# 2020_Main_Board_-_Schematic.net
KiCad netlist of a schematic drawn in EasyEDA
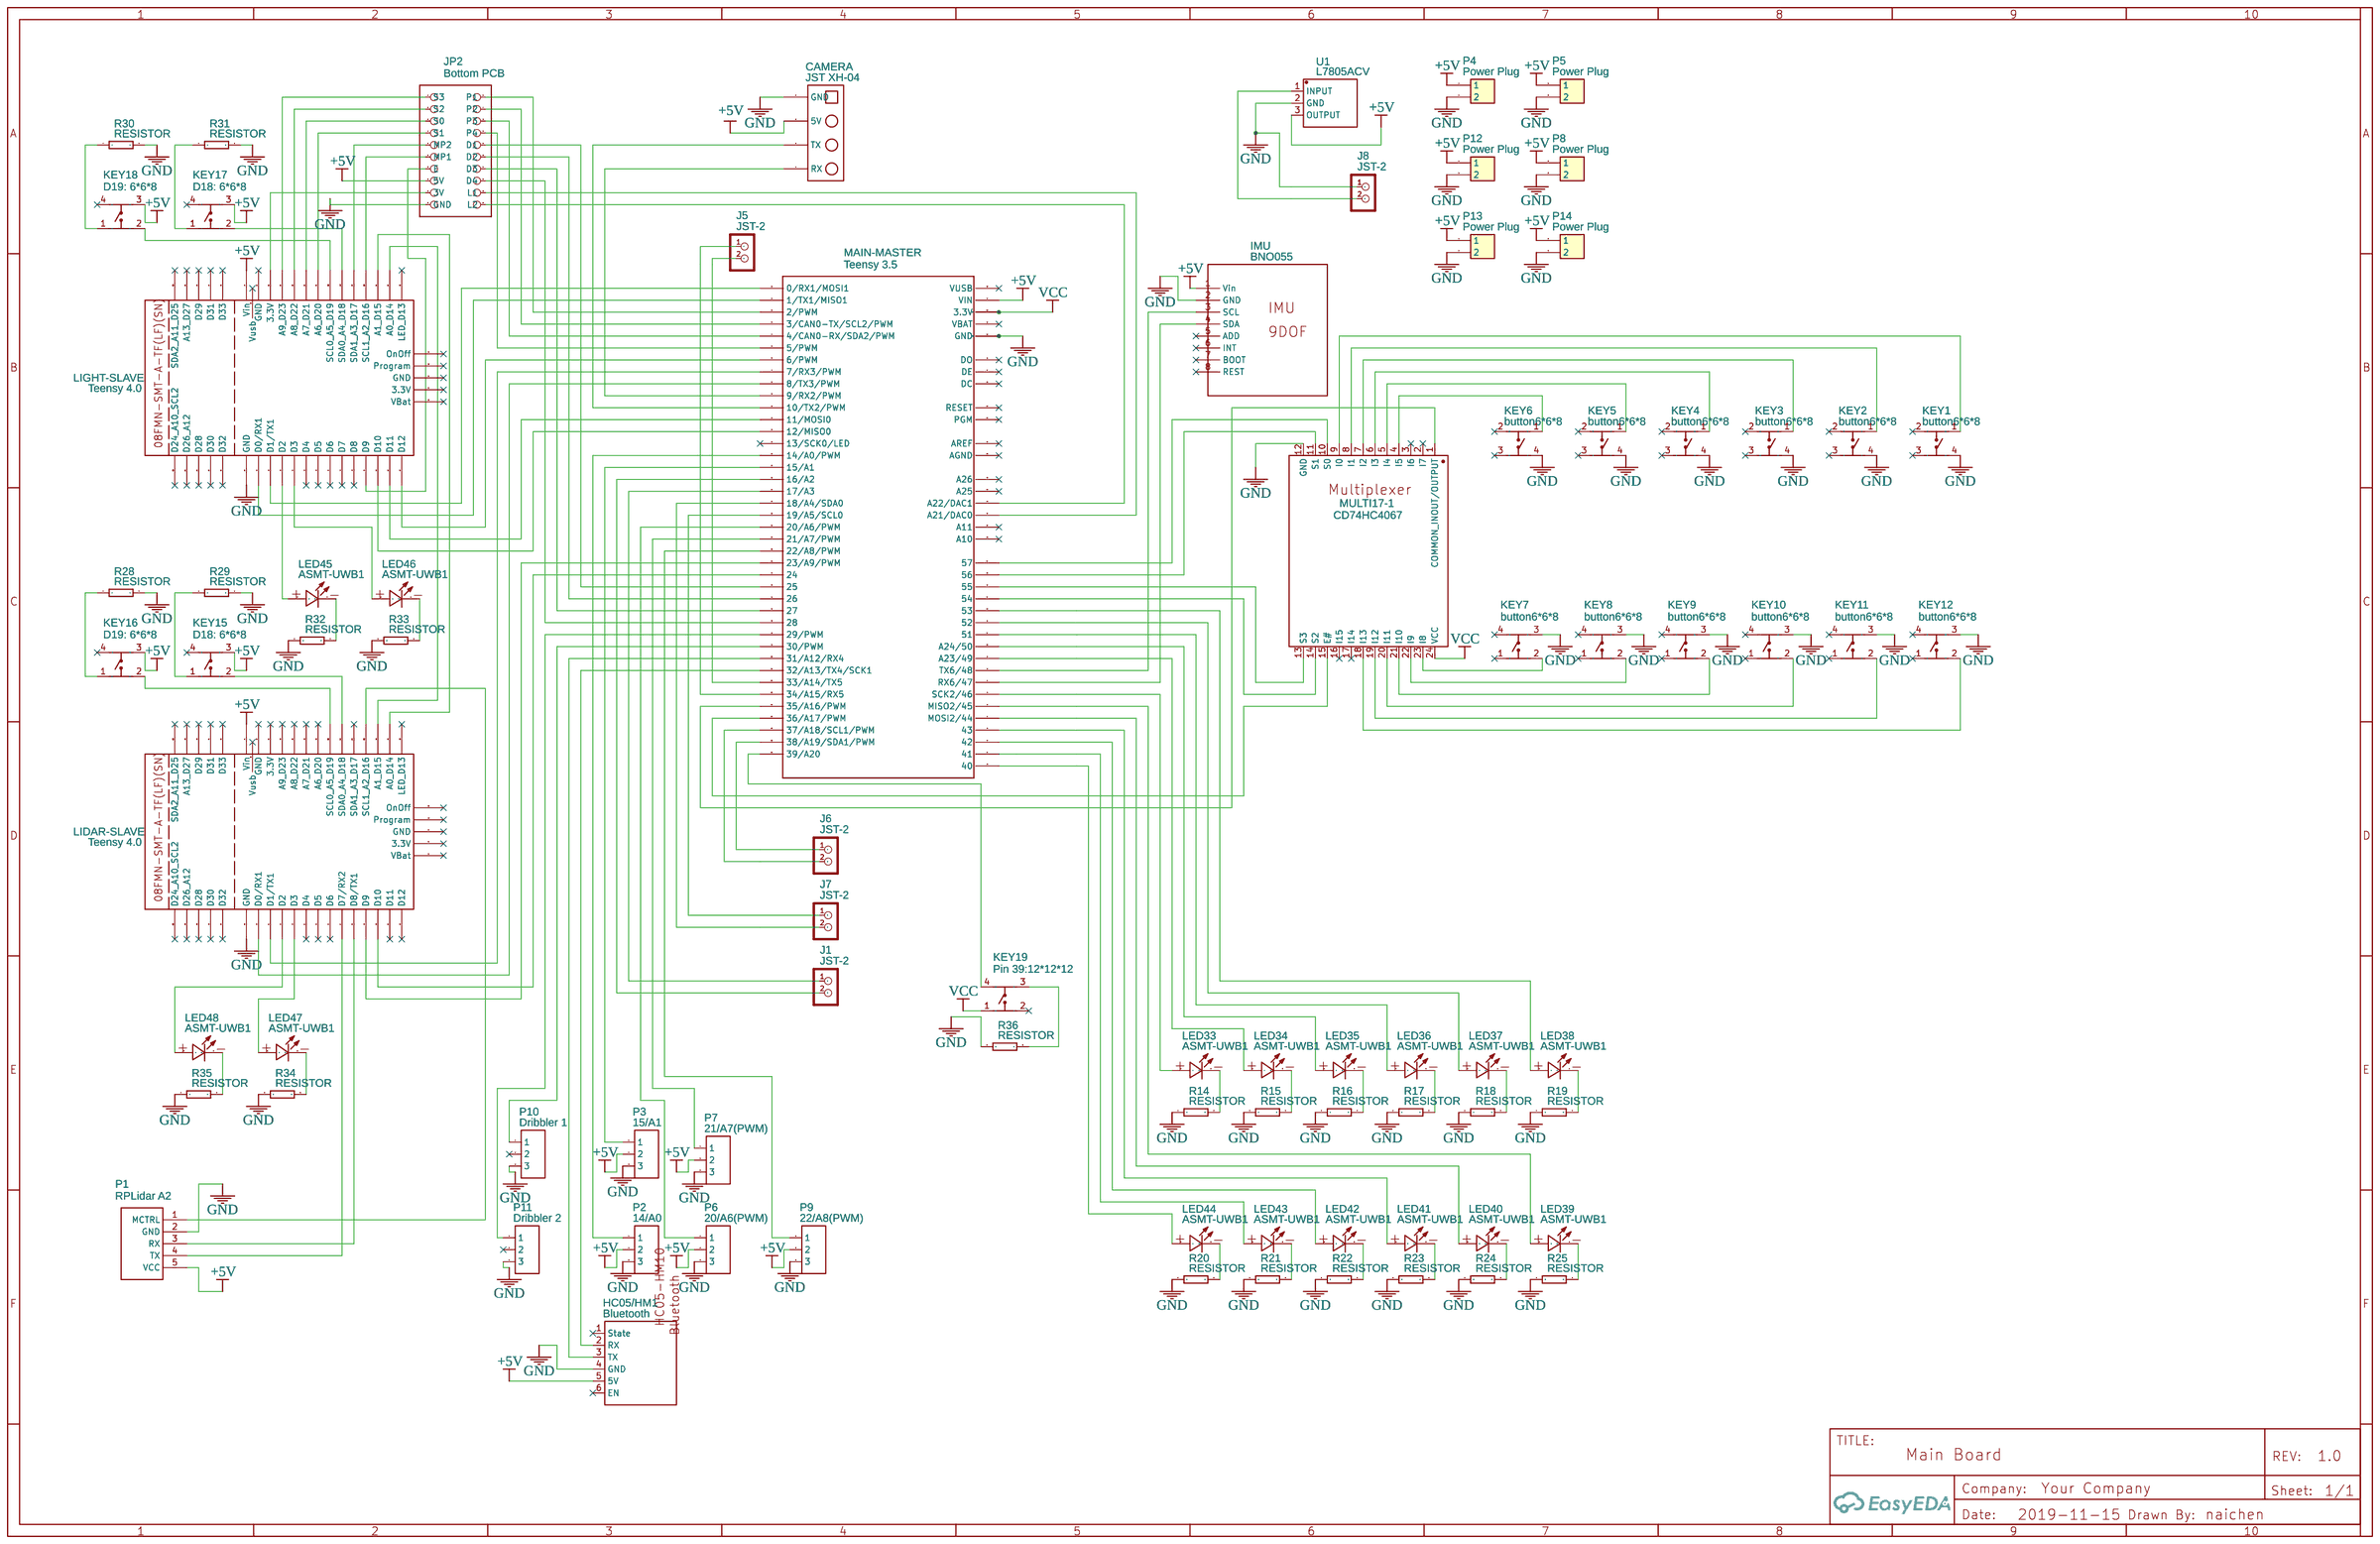
[diagram p0: schematic sheet]

(export (version "E")
  (design (tool "Eeschema 10.0.6"))
  (components
    (comp (ref "CAMERA")
      (value "JST XH-04")
      (fields (field (name "BOM_Manufacturer Part") "JST_XH CONNECTOR"))
      (libsource (lib "") (part "Unknown_680_105"))
    )
    (comp (ref "HC05/HM1") (value "Bluetooth") (libsource (lib "") (part "Unknown_530_1130")))
    (comp (ref "IMU") (value "BNO055") (libsource (lib "") (part "Unknown_1050_260")))
    (comp (ref "J1") (value "JST-2") (libsource (lib "") (part "JST-2")))
    (comp (ref "J5") (value "JST-2") (libsource (lib "") (part "JST-2")))
    (comp (ref "J6") (value "JST-2") (libsource (lib "") (part "JST-2")))
    (comp (ref "J7") (value "JST-2") (libsource (lib "") (part "JST-2")))
    (comp (ref "J8") (value "JST-2") (libsource (lib "") (part "JST-2")))
    (comp (ref "JP2") (value "Bottom PCB") (libsource (lib "") (part "Unknown_375_120")))
    (comp (ref "KEY1")
      (value "button6*6*8")
      (fields (field (name "BOM_Supplier Part") "C59982"))
      (libsource (lib "") (part "Unknown_1615_365"))
    )
    (comp (ref "KEY2")
      (value "button6*6*8")
      (fields (field (name "BOM_Supplier Part") "C59982"))
      (libsource (lib "") (part "Unknown_1545_365"))
    )
    (comp (ref "KEY3")
      (value "button6*6*8")
      (fields (field (name "BOM_Supplier Part") "C59982"))
      (libsource (lib "") (part "Unknown_1475_365"))
    )
    (comp (ref "KEY4")
      (value "button6*6*8")
      (fields (field (name "BOM_Supplier Part") "C59982"))
      (libsource (lib "") (part "Unknown_1405_365"))
    )
    (comp (ref "KEY5")
      (value "button6*6*8")
      (fields (field (name "BOM_Supplier Part") "C59982"))
      (libsource (lib "") (part "Unknown_1335_365"))
    )
    (comp (ref "KEY6")
      (value "button6*6*8")
      (fields (field (name "BOM_Supplier Part") "C59982"))
      (libsource (lib "") (part "Unknown_1265_365"))
    )
    (comp (ref "KEY7")
      (value "button6*6*8")
      (fields (field (name "BOM_Supplier Part") "C59982"))
      (libsource (lib "") (part "Unknown_1265_535"))
    )
    (comp (ref "KEY8")
      (value "button6*6*8")
      (fields (field (name "BOM_Supplier Part") "C59982"))
      (libsource (lib "") (part "Unknown_1335_535"))
    )
    (comp (ref "KEY9")
      (value "button6*6*8")
      (fields (field (name "BOM_Supplier Part") "C59982"))
      (libsource (lib "") (part "Unknown_1405_535"))
    )
    (comp (ref "KEY10")
      (value "button6*6*8")
      (fields (field (name "BOM_Supplier Part") "C59982"))
      (libsource (lib "") (part "Unknown_1475_535"))
    )
    (comp (ref "KEY11")
      (value "button6*6*8")
      (fields (field (name "BOM_Supplier Part") "C59982"))
      (libsource (lib "") (part "Unknown_1545_535"))
    )
    (comp (ref "KEY12")
      (value "button6*6*8")
      (fields (field (name "BOM_Supplier Part") "C59982"))
      (libsource (lib "") (part "Unknown_1615_535"))
    )
    (comp (ref "KEY15")
      (value "D18: 6*6*8")
      (fields
        (field (name "BOM_Manufacturer Part") "button6*6*8")
        (field (name "BOM_Supplier Part") "C59982")
      )
      (libsource (lib "") (part "Unknown_170_550"))
    )
    (comp (ref "KEY16")
      (value "D19: 6*6*8")
      (fields
        (field (name "BOM_Manufacturer Part") "button6*6*8")
        (field (name "BOM_Supplier Part") "C59982")
      )
      (libsource (lib "") (part "Unknown_95_550"))
    )
    (comp (ref "KEY17")
      (value "D18: 6*6*8")
      (fields
        (field (name "BOM_Manufacturer Part") "button6*6*8")
        (field (name "BOM_Supplier Part") "C59982")
      )
      (libsource (lib "") (part "Unknown_170_175"))
    )
    (comp (ref "KEY18")
      (value "D19: 6*6*8")
      (fields
        (field (name "BOM_Manufacturer Part") "button6*6*8")
        (field (name "BOM_Supplier Part") "C59982")
      )
      (libsource (lib "") (part "Unknown_95_175"))
    )
    (comp (ref "KEY19")
      (value "Pin 39:12*12*12")
      (fields
        (field (name "BOM_Manufacturer Part") "Switch 12*12*12")
        (field (name "BOM_Supplier Part") "C14121")
      )
      (libsource (lib "") (part "Unknown_835_830"))
    )
    (comp (ref "LED33")
      (value "ASMT-UWB1")
      (fields
        (field (name "BOM_Manufacturer Part") "ASMT-BG20-AS000")
        (field (name "BOM_Supplier Part") "C188684")
      )
      (libsource (lib "") (part "Unknown_995_890"))
    )
    (comp (ref "LED34")
      (value "ASMT-UWB1")
      (fields
        (field (name "BOM_Manufacturer Part") "ASMT-BG20-AS000")
        (field (name "BOM_Supplier Part") "C188684")
      )
      (libsource (lib "") (part "Unknown_1055_890"))
    )
    (comp (ref "LED35")
      (value "ASMT-UWB1")
      (fields
        (field (name "BOM_Manufacturer Part") "ASMT-BG20-AS000")
        (field (name "BOM_Supplier Part") "C188684")
      )
      (libsource (lib "") (part "Unknown_1115_890"))
    )
    (comp (ref "LED36")
      (value "ASMT-UWB1")
      (fields
        (field (name "BOM_Manufacturer Part") "ASMT-BG20-AS000")
        (field (name "BOM_Supplier Part") "C188684")
      )
      (libsource (lib "") (part "Unknown_1175_890"))
    )
    (comp (ref "LED37")
      (value "ASMT-UWB1")
      (fields
        (field (name "BOM_Manufacturer Part") "ASMT-BG20-AS000")
        (field (name "BOM_Supplier Part") "C188684")
      )
      (libsource (lib "") (part "Unknown_1235_890"))
    )
    (comp (ref "LED38")
      (value "ASMT-UWB1")
      (fields
        (field (name "BOM_Manufacturer Part") "ASMT-BG20-AS000")
        (field (name "BOM_Supplier Part") "C188684")
      )
      (libsource (lib "") (part "Unknown_1295_890"))
    )
    (comp (ref "LED39")
      (value "ASMT-UWB1")
      (fields
        (field (name "BOM_Manufacturer Part") "ASMT-BG20-AS000")
        (field (name "BOM_Supplier Part") "C188684")
      )
      (libsource (lib "") (part "Unknown_1295_1035"))
    )
    (comp (ref "LED40")
      (value "ASMT-UWB1")
      (fields
        (field (name "BOM_Manufacturer Part") "ASMT-BG20-AS000")
        (field (name "BOM_Supplier Part") "C188684")
      )
      (libsource (lib "") (part "Unknown_1235_1035"))
    )
    (comp (ref "LED41")
      (value "ASMT-UWB1")
      (fields
        (field (name "BOM_Manufacturer Part") "ASMT-BG20-AS000")
        (field (name "BOM_Supplier Part") "C188684")
      )
      (libsource (lib "") (part "Unknown_1175_1035"))
    )
    (comp (ref "LED42")
      (value "ASMT-UWB1")
      (fields
        (field (name "BOM_Manufacturer Part") "ASMT-BG20-AS000")
        (field (name "BOM_Supplier Part") "C188684")
      )
      (libsource (lib "") (part "Unknown_1115_1035"))
    )
    (comp (ref "LED43")
      (value "ASMT-UWB1")
      (fields
        (field (name "BOM_Manufacturer Part") "ASMT-BG20-AS000")
        (field (name "BOM_Supplier Part") "C188684")
      )
      (libsource (lib "") (part "Unknown_1055_1035"))
    )
    (comp (ref "LED44")
      (value "ASMT-UWB1")
      (fields
        (field (name "BOM_Manufacturer Part") "ASMT-BG20-AS000")
        (field (name "BOM_Supplier Part") "C188684")
      )
      (libsource (lib "") (part "Unknown_995_1035"))
    )
    (comp (ref "LED45")
      (value "ASMT-UWB1")
      (fields
        (field (name "BOM_Manufacturer Part") "ASMT-BG20-AS000")
        (field (name "BOM_Supplier Part") "C188684")
      )
      (libsource (lib "") (part "Unknown_255_495"))
    )
    (comp (ref "LED46")
      (value "ASMT-UWB1")
      (fields
        (field (name "BOM_Manufacturer Part") "ASMT-BG20-AS000")
        (field (name "BOM_Supplier Part") "C188684")
      )
      (libsource (lib "") (part "Unknown_325_495"))
    )
    (comp (ref "LED47")
      (value "ASMT-UWB1")
      (fields
        (field (name "BOM_Manufacturer Part") "ASMT-BG20-AS000")
        (field (name "BOM_Supplier Part") "C188684")
      )
      (libsource (lib "") (part "Unknown_230_875"))
    )
    (comp (ref "LED48")
      (value "ASMT-UWB1")
      (fields
        (field (name "BOM_Manufacturer Part") "ASMT-BG20-AS000")
        (field (name "BOM_Supplier Part") "C188684")
      )
      (libsource (lib "") (part "Unknown_160_875"))
    )
    (comp (ref "LIDAR-SLAVE") (value "Teensy 4.0") (libsource (lib "") (part "Unknown_210_690")))
    (comp (ref "LIGHT-SLAVE") (value "Teensy 4.0") (libsource (lib "") (part "Unknown_210_310")))
    (comp (ref "MAIN-MASTER") (value "Teensy 3.5") (libsource (lib "") (part "Unknown_730_435")))
    (comp (ref "MULTI17-1") (value "CD74HC4067") (libsource (lib "") (part "Unknown_1140_455")))
    (comp (ref "P1") (value "RPLidar A2") (libsource (lib "") (part "Unknown_130_1055")))
    (comp (ref "P2")
      (value "14/A0")
      (fields
        (field (name "BOM_Manufacturer Part") "Header-Female-2.54_1x3")
        (field (name "BOM_Supplier Part") "C146243")
      )
      (libsource (lib "") (part "Unknown_530_1040"))
    )
    (comp (ref "P3")
      (value "15/A1")
      (fields
        (field (name "BOM_Manufacturer Part") "Header-Female-2.54_1x3")
        (field (name "BOM_Supplier Part") "C146243")
      )
      (libsource (lib "") (part "Unknown_530_960"))
    )
    (comp (ref "P4")
      (value "Power Plug")
      (fields
        (field (name "BOM_Manufacturer Part") "Header-Female-2.54_1x2")
        (field (name "BOM_Supplier Part") "C49661")
      )
      (libsource (lib "") (part "Unknown_1220_70"))
    )
    (comp (ref "P5")
      (value "Power Plug")
      (fields
        (field (name "BOM_Manufacturer Part") "Header-Female-2.54_1x2")
        (field (name "BOM_Supplier Part") "C49661")
      )
      (libsource (lib "") (part "Unknown_1295_70"))
    )
    (comp (ref "P6")
      (value "20/A6(PWM)")
      (fields
        (field (name "BOM_Manufacturer Part") "Header-Female-2.54_1x3")
        (field (name "BOM_Supplier Part") "C146243")
      )
      (libsource (lib "") (part "Unknown_590_1040"))
    )
    (comp (ref "P7")
      (value "21/A7(PWM)")
      (fields
        (field (name "BOM_Manufacturer Part") "Header-Female-2.54_1x3")
        (field (name "BOM_Supplier Part") "C146243")
      )
      (libsource (lib "") (part "Unknown_590_965"))
    )
    (comp (ref "P8")
      (value "Power Plug")
      (fields
        (field (name "BOM_Manufacturer Part") "Header-Female-2.54_1x2")
        (field (name "BOM_Supplier Part") "C49661")
      )
      (libsource (lib "") (part "Unknown_1295_135"))
    )
    (comp (ref "P9")
      (value "22/A8(PWM)")
      (fields
        (field (name "BOM_Manufacturer Part") "Header-Female-2.54_1x3")
        (field (name "BOM_Supplier Part") "C146243")
      )
      (libsource (lib "") (part "Unknown_670_1040"))
    )
    (comp (ref "P10")
      (value "Dribbler 1")
      (fields
        (field (name "BOM_Manufacturer Part") "Header-Female-2.54_1x3")
        (field (name "BOM_Supplier Part") "C146243")
      )
      (libsource (lib "") (part "Unknown_435_960"))
    )
    (comp (ref "P11")
      (value "Dribbler 2")
      (fields
        (field (name "BOM_Manufacturer Part") "Header-Female-2.54_1x3")
        (field (name "BOM_Supplier Part") "C146243")
      )
      (libsource (lib "") (part "Unknown_430_1040"))
    )
    (comp (ref "P12")
      (value "Power Plug")
      (fields
        (field (name "BOM_Manufacturer Part") "Header-Female-2.54_1x2")
        (field (name "BOM_Supplier Part") "C49661")
      )
      (libsource (lib "") (part "Unknown_1220_135"))
    )
    (comp (ref "P13")
      (value "Power Plug")
      (fields
        (field (name "BOM_Manufacturer Part") "Header-Female-2.54_1x2")
        (field (name "BOM_Supplier Part") "C49661")
      )
      (libsource (lib "") (part "Unknown_1220_200"))
    )
    (comp (ref "P14")
      (value "Power Plug")
      (fields
        (field (name "BOM_Manufacturer Part") "Header-Female-2.54_1x2")
        (field (name "BOM_Supplier Part") "C49661")
      )
      (libsource (lib "") (part "Unknown_1295_200"))
    )
    (comp (ref "R14") (value "RESISTOR") (libsource (lib "") (part "Unknown_995_925")))
    (comp (ref "R15") (value "RESISTOR") (libsource (lib "") (part "Unknown_1055_925")))
    (comp (ref "R16") (value "RESISTOR") (libsource (lib "") (part "Unknown_1115_925")))
    (comp (ref "R17") (value "RESISTOR") (libsource (lib "") (part "Unknown_1175_925")))
    (comp (ref "R18") (value "RESISTOR") (libsource (lib "") (part "Unknown_1235_925")))
    (comp (ref "R19") (value "RESISTOR") (libsource (lib "") (part "Unknown_1295_925")))
    (comp (ref "R20") (value "RESISTOR") (libsource (lib "") (part "Unknown_995_1065")))
    (comp (ref "R21") (value "RESISTOR") (libsource (lib "") (part "Unknown_1055_1065")))
    (comp (ref "R22") (value "RESISTOR") (libsource (lib "") (part "Unknown_1115_1065")))
    (comp (ref "R23") (value "RESISTOR") (libsource (lib "") (part "Unknown_1175_1065")))
    (comp (ref "R24") (value "RESISTOR") (libsource (lib "") (part "Unknown_1235_1065")))
    (comp (ref "R25") (value "RESISTOR") (libsource (lib "") (part "Unknown_1295_1065")))
    (comp (ref "R28") (value "RESISTOR") (libsource (lib "") (part "Unknown_95_490")))
    (comp (ref "R29") (value "RESISTOR") (libsource (lib "") (part "Unknown_175_490")))
    (comp (ref "R30") (value "RESISTOR") (libsource (lib "") (part "Unknown_95_115")))
    (comp (ref "R31") (value "RESISTOR") (libsource (lib "") (part "Unknown_175_115")))
    (comp (ref "R32") (value "RESISTOR") (libsource (lib "") (part "Unknown_255_530")))
    (comp (ref "R33") (value "RESISTOR") (libsource (lib "") (part "Unknown_325_530")))
    (comp (ref "R34") (value "RESISTOR") (libsource (lib "") (part "Unknown_230_910")))
    (comp (ref "R35") (value "RESISTOR") (libsource (lib "") (part "Unknown_160_910")))
    (comp (ref "R36") (value "RESISTOR") (libsource (lib "") (part "Unknown_835_870")))
    (comp (ref "U1")
      (value "L7805ACV")
      (fields (field (name "BOM_Supplier Part") "C192854"))
      (libsource (lib "") (part "Unknown_1100_80"))
    )
  )
  (nets
    (net (code "1") (name "+5V") (class "Default")
      (node (ref "CAMERA") (pin "2") (pinfunction "5V_2") (pintype "unspecified"))
      (node (ref "HC05/HM1") (pin "5") (pinfunction "5V_5") (pintype "unspecified"))
      (node (ref "IMU") (pin "1") (pinfunction "Vin_1") (pintype "unspecified"))
      (node (ref "JP2") (pin "15") (pinfunction "5V_15") (pintype "unspecified"))
      (node (ref "KEY15") (pin "3") (pinfunction "3_3") (pintype "unspecified"))
      (node (ref "KEY16") (pin "3") (pinfunction "3_3") (pintype "unspecified"))
      (node (ref "KEY17") (pin "3") (pinfunction "3_3") (pintype "unspecified"))
      (node (ref "KEY18") (pin "3") (pinfunction "3_3") (pintype "unspecified"))
      (node (ref "LIDAR-SLAVE") (pin "Vin") (pinfunction "Vin_Vin") (pintype "passive"))
      (node (ref "LIGHT-SLAVE") (pin "Vin") (pinfunction "Vin_Vin") (pintype "passive"))
      (node (ref "MAIN-MASTER") (pin "VIN") (pinfunction "VIN_VIN") (pintype "bidirectional"))
      (node (ref "P1") (pin "5") (pinfunction "VCC_5") (pintype "unspecified"))
      (node (ref "P12") (pin "1") (pinfunction "1_1") (pintype "input"))
      (node (ref "P13") (pin "1") (pinfunction "1_1") (pintype "input"))
      (node (ref "P14") (pin "1") (pinfunction "1_1") (pintype "input"))
      (node (ref "P2") (pin "2") (pinfunction "2_2") (pintype "input"))
      (node (ref "P3") (pin "2") (pinfunction "2_2") (pintype "input"))
      (node (ref "P4") (pin "1") (pinfunction "1_1") (pintype "input"))
      (node (ref "P5") (pin "1") (pinfunction "1_1") (pintype "input"))
      (node (ref "P6") (pin "2") (pinfunction "2_2") (pintype "input"))
      (node (ref "P7") (pin "2") (pinfunction "2_2") (pintype "input"))
      (node (ref "P8") (pin "1") (pinfunction "1_1") (pintype "input"))
      (node (ref "P9") (pin "2") (pinfunction "2_2") (pintype "input"))
      (node (ref "U1") (pin "3") (pinfunction "OUTPUT_3") (pintype "unspecified"))
    )
    (net (code "2") (name "GND") (class "Default")
      (node (ref "CAMERA") (pin "1") (pinfunction "GND_1") (pintype "unspecified"))
      (node (ref "HC05/HM1") (pin "4") (pinfunction "GND_4") (pintype "unspecified"))
      (node (ref "IMU") (pin "2") (pinfunction "GND_2") (pintype "unspecified"))
      (node (ref "J8") (pin "1") (pinfunction "1_1") (pintype "unspecified"))
      (node (ref "JP2") (pin "19") (pinfunction "GND_19") (pintype "unspecified"))
      (node (ref "KEY1") (pin "4") (pinfunction "4_4") (pintype "unspecified"))
      (node (ref "KEY10") (pin "3") (pinfunction "3_3") (pintype "unspecified"))
      (node (ref "KEY11") (pin "3") (pinfunction "3_3") (pintype "unspecified"))
      (node (ref "KEY12") (pin "3") (pinfunction "3_3") (pintype "unspecified"))
      (node (ref "KEY2") (pin "4") (pinfunction "4_4") (pintype "unspecified"))
      (node (ref "KEY3") (pin "4") (pinfunction "4_4") (pintype "unspecified"))
      (node (ref "KEY4") (pin "4") (pinfunction "4_4") (pintype "unspecified"))
      (node (ref "KEY5") (pin "4") (pinfunction "4_4") (pintype "unspecified"))
      (node (ref "KEY6") (pin "4") (pinfunction "4_4") (pintype "unspecified"))
      (node (ref "KEY7") (pin "3") (pinfunction "3_3") (pintype "unspecified"))
      (node (ref "KEY8") (pin "3") (pinfunction "3_3") (pintype "unspecified"))
      (node (ref "KEY9") (pin "3") (pinfunction "3_3") (pintype "unspecified"))
      (node (ref "LIDAR-SLAVE") (pin "GND") (pinfunction "GND_GND") (pintype "input"))
      (node (ref "LIGHT-SLAVE") (pin "GND") (pinfunction "GND_GND") (pintype "input"))
      (node (ref "MAIN-MASTER") (pin "GND") (pinfunction "GND_GND") (pintype "bidirectional"))
      (node (ref "MAIN-MASTER") (pin "GND1") (pinfunction "GND_GND1") (pintype "bidirectional"))
      (node (ref "MAIN-MASTER") (pin "GND2") (pinfunction "GND_GND2") (pintype "bidirectional"))
      (node (ref "MAIN-MASTER") (pin "GND3") (pinfunction "GND_GND3") (pintype "bidirectional"))
      (node (ref "MAIN-MASTER") (pin "GND4") (pinfunction "GND_GND4") (pintype "bidirectional"))
      (node (ref "MAIN-MASTER") (pin "GND5") (pinfunction "GND_GND5") (pintype "bidirectional"))
      (node (ref "MAIN-MASTER") (pin "GND6") (pinfunction "GND_GND6") (pintype "bidirectional"))
      (node (ref "MULTI17-1") (pin "12") (pinfunction "GND_12") (pintype "unspecified"))
      (node (ref "P1") (pin "2") (pinfunction "GND_2") (pintype "unspecified"))
      (node (ref "P10") (pin "3") (pinfunction "3_3") (pintype "input"))
      (node (ref "P11") (pin "3") (pinfunction "3_3") (pintype "input"))
      (node (ref "P12") (pin "2") (pinfunction "2_2") (pintype "input"))
      (node (ref "P13") (pin "2") (pinfunction "2_2") (pintype "input"))
      (node (ref "P14") (pin "2") (pinfunction "2_2") (pintype "input"))
      (node (ref "P2") (pin "3") (pinfunction "3_3") (pintype "input"))
      (node (ref "P3") (pin "3") (pinfunction "3_3") (pintype "input"))
      (node (ref "P4") (pin "2") (pinfunction "2_2") (pintype "input"))
      (node (ref "P5") (pin "2") (pinfunction "2_2") (pintype "input"))
      (node (ref "P6") (pin "3") (pinfunction "3_3") (pintype "input"))
      (node (ref "P7") (pin "3") (pinfunction "3_3") (pintype "input"))
      (node (ref "P8") (pin "2") (pinfunction "2_2") (pintype "input"))
      (node (ref "P9") (pin "3") (pinfunction "3_3") (pintype "input"))
      (node (ref "R14") (pin "1") (pinfunction "1_1") (pintype "unspecified"))
      (node (ref "R15") (pin "1") (pinfunction "1_1") (pintype "unspecified"))
      (node (ref "R16") (pin "1") (pinfunction "1_1") (pintype "unspecified"))
      (node (ref "R17") (pin "1") (pinfunction "1_1") (pintype "unspecified"))
      (node (ref "R18") (pin "1") (pinfunction "1_1") (pintype "unspecified"))
      (node (ref "R19") (pin "1") (pinfunction "1_1") (pintype "unspecified"))
      (node (ref "R20") (pin "1") (pinfunction "1_1") (pintype "unspecified"))
      (node (ref "R21") (pin "1") (pinfunction "1_1") (pintype "unspecified"))
      (node (ref "R22") (pin "1") (pinfunction "1_1") (pintype "unspecified"))
      (node (ref "R23") (pin "1") (pinfunction "1_1") (pintype "unspecified"))
      (node (ref "R24") (pin "1") (pinfunction "1_1") (pintype "unspecified"))
      (node (ref "R25") (pin "1") (pinfunction "1_1") (pintype "unspecified"))
      (node (ref "R28") (pin "2") (pinfunction "2_2") (pintype "unspecified"))
      (node (ref "R29") (pin "2") (pinfunction "2_2") (pintype "unspecified"))
      (node (ref "R30") (pin "2") (pinfunction "2_2") (pintype "unspecified"))
      (node (ref "R31") (pin "2") (pinfunction "2_2") (pintype "unspecified"))
      (node (ref "R32") (pin "1") (pinfunction "1_1") (pintype "unspecified"))
      (node (ref "R33") (pin "1") (pinfunction "1_1") (pintype "unspecified"))
      (node (ref "R34") (pin "1") (pinfunction "1_1") (pintype "unspecified"))
      (node (ref "R35") (pin "1") (pinfunction "1_1") (pintype "unspecified"))
      (node (ref "R36") (pin "1") (pinfunction "1_1") (pintype "unspecified"))
      (node (ref "U1") (pin "2") (pinfunction "GND_2") (pintype "unspecified"))
    )
    (net (code "3") (name "Net-(CAMERA-RX)") (class "Default")
      (node (ref "CAMERA") (pin "4") (pinfunction "RX_4") (pintype "unspecified"))
      (node (ref "MAIN-MASTER") (pin "9") (pinfunction "9/RX2/PWM_9") (pintype "bidirectional"))
    )
    (net (code "4") (name "Net-(CAMERA-TX)") (class "Default")
      (node (ref "CAMERA") (pin "3") (pinfunction "TX_3") (pintype "unspecified"))
      (node (ref "MAIN-MASTER") (pin "10") (pinfunction "10/TX2/PWM_10") (pintype "bidirectional"))
    )
    (net (code "5") (name "Net-(HC05/HM1-RX)") (class "Default")
      (node (ref "HC05/HM1") (pin "2") (pinfunction "RX_2") (pintype "unspecified"))
      (node (ref "MAIN-MASTER") (pin "32/A13") (pinfunction "32/A13/TX4/SCK1_32/A13") (pintype "bidirectional"))
    )
    (net (code "6") (name "Net-(HC05/HM1-TX)") (class "Default")
      (node (ref "HC05/HM1") (pin "3") (pinfunction "TX_3") (pintype "unspecified"))
      (node (ref "MAIN-MASTER") (pin "31/A12") (pinfunction "31/A12/RX4_31/A12") (pintype "bidirectional"))
    )
    (net (code "7") (name "Net-(IMU-SCL)") (class "Default")
      (node (ref "IMU") (pin "3") (pinfunction "SCL_3") (pintype "unspecified"))
      (node (ref "MAIN-MASTER") (pin "48") (pinfunction "TX6/48_48") (pintype "bidirectional"))
    )
    (net (code "8") (name "Net-(IMU-SDA)") (class "Default")
      (node (ref "IMU") (pin "4") (pinfunction "SDA_4") (pintype "unspecified"))
      (node (ref "MAIN-MASTER") (pin "47") (pinfunction "RX6/47_47") (pintype "bidirectional"))
    )
    (net (code "9") (name "Net-(J1-Pad1)") (class "Default")
      (node (ref "J1") (pin "1") (pinfunction "1_1") (pintype "unspecified"))
      (node (ref "MAIN-MASTER") (pin "17/A3") (pinfunction "17/A3_17/A3") (pintype "bidirectional"))
    )
    (net (code "10") (name "Net-(J1-Pad2)") (class "Default")
      (node (ref "J1") (pin "2") (pinfunction "2_2") (pintype "unspecified"))
      (node (ref "MAIN-MASTER") (pin "16/A2") (pinfunction "16/A2_16/A2") (pintype "bidirectional"))
    )
    (net (code "11") (name "Net-(JP2-3V)") (class "Default")
      (node (ref "JP2") (pin "17") (pinfunction "3V_17") (pintype "unspecified"))
      (node (ref "LIGHT-SLAVE") (pin "3.3V") (pinfunction "3.3V_3.3V") (pintype "bidirectional"))
    )
    (net (code "12") (name "Net-(JP2-D1)") (class "Default")
      (node (ref "JP2") (pin "10") (pinfunction "D1_10") (pintype "unspecified"))
      (node (ref "MAIN-MASTER") (pin "25") (pinfunction "25_25") (pintype "bidirectional"))
    )
    (net (code "13") (name "Net-(JP2-D2)") (class "Default")
      (node (ref "JP2") (pin "12") (pinfunction "D2_12") (pintype "unspecified"))
      (node (ref "MAIN-MASTER") (pin "26") (pinfunction "26_26") (pintype "bidirectional"))
    )
    (net (code "14") (name "Net-(JP2-D3)") (class "Default")
      (node (ref "JP2") (pin "14") (pinfunction "D3_14") (pintype "unspecified"))
      (node (ref "MAIN-MASTER") (pin "27") (pinfunction "27_27") (pintype "bidirectional"))
    )
    (net (code "15") (name "Net-(JP2-D4)") (class "Default")
      (node (ref "JP2") (pin "16") (pinfunction "D4_16") (pintype "unspecified"))
      (node (ref "MAIN-MASTER") (pin "28") (pinfunction "28_28") (pintype "bidirectional"))
    )
    (net (code "16") (name "Net-(JP2-E)") (class "Default")
      (node (ref "JP2") (pin "13") (pinfunction "E_13") (pintype "unspecified"))
      (node (ref "LIGHT-SLAVE") (pin "D9") (pinfunction "D9_D9") (pintype "bidirectional"))
    )
    (net (code "17") (name "Net-(JP2-L1)") (class "Default")
      (node (ref "JP2") (pin "18") (pinfunction "L1_18") (pintype "unspecified"))
      (node (ref "MAIN-MASTER") (pin "A21") (pinfunction "A21/DAC0_A21") (pintype "bidirectional"))
    )
    (net (code "18") (name "Net-(JP2-L2)") (class "Default")
      (node (ref "JP2") (pin "20") (pinfunction "L2_20") (pintype "unspecified"))
      (node (ref "MAIN-MASTER") (pin "A22") (pinfunction "A22/DAC1_A22") (pintype "bidirectional"))
    )
    (net (code "19") (name "Net-(JP2-MP1)") (class "Default")
      (node (ref "JP2") (pin "11") (pinfunction "MP1_11") (pintype "unspecified"))
      (node (ref "LIGHT-SLAVE") (pin "SCL1_A2_D16") (pinfunction "SCL1_A2_D16_SCL1_A2_D16") (pintype "bidirectional"))
    )
    (net (code "20") (name "Net-(JP2-MP2)") (class "Default")
      (node (ref "JP2") (pin "9") (pinfunction "MP2_9") (pintype "unspecified"))
      (node (ref "LIGHT-SLAVE") (pin "SDA1_A3_D17") (pinfunction "SDA1_A3_D17_SDA1_A3_D17") (pintype "bidirectional"))
    )
    (net (code "21") (name "Net-(JP2-P1)") (class "Default")
      (node (ref "JP2") (pin "2") (pinfunction "P1_2") (pintype "unspecified"))
      (node (ref "MAIN-MASTER") (pin "2") (pinfunction "2/PWM_2") (pintype "bidirectional"))
    )
    (net (code "22") (name "Net-(JP2-P2)") (class "Default")
      (node (ref "JP2") (pin "4") (pinfunction "P2_4") (pintype "unspecified"))
      (node (ref "MAIN-MASTER") (pin "3") (pinfunction "3/CAN0-TX/SCL2/PWM_3") (pintype "bidirectional"))
    )
    (net (code "23") (name "Net-(JP2-P3)") (class "Default")
      (node (ref "JP2") (pin "6") (pinfunction "P3_6") (pintype "unspecified"))
      (node (ref "MAIN-MASTER") (pin "4") (pinfunction "4/CAN0-RX/SDA2/PWM_4") (pintype "bidirectional"))
    )
    (net (code "24") (name "Net-(JP2-P4)") (class "Default")
      (node (ref "JP2") (pin "8") (pinfunction "P4_8") (pintype "unspecified"))
      (node (ref "MAIN-MASTER") (pin "5") (pinfunction "5/PWM_5") (pintype "bidirectional"))
    )
    (net (code "25") (name "Net-(JP2-S0)") (class "Default")
      (node (ref "JP2") (pin "5") (pinfunction "S0_5") (pintype "unspecified"))
      (node (ref "LIGHT-SLAVE") (pin "A7_D21") (pinfunction "A7_D21_A7_D21") (pintype "bidirectional"))
    )
    (net (code "26") (name "Net-(JP2-S1)") (class "Default")
      (node (ref "JP2") (pin "7") (pinfunction "S1_7") (pintype "unspecified"))
      (node (ref "LIGHT-SLAVE") (pin "A6_D20") (pinfunction "A6_D20_A6_D20") (pintype "bidirectional"))
    )
    (net (code "27") (name "Net-(JP2-S2)") (class "Default")
      (node (ref "JP2") (pin "3") (pinfunction "S2_3") (pintype "unspecified"))
      (node (ref "LIGHT-SLAVE") (pin "A8_D22") (pinfunction "A8_D22_A8_D22") (pintype "bidirectional"))
    )
    (net (code "28") (name "Net-(JP2-S3)") (class "Default")
      (node (ref "JP2") (pin "1") (pinfunction "S3_1") (pintype "unspecified"))
      (node (ref "LIGHT-SLAVE") (pin "A9_D23") (pinfunction "A9_D23_A9_D23") (pintype "bidirectional"))
    )
    (net (code "29") (name "Net-(KEY15-Pad1)") (class "Default")
      (node (ref "KEY15") (pin "1") (pinfunction "1_1") (pintype "unspecified"))
      (node (ref "R29") (pin "1") (pinfunction "1_1") (pintype "unspecified"))
    )
    (net (code "30") (name "Net-(KEY15-Pad2)") (class "Default")
      (node (ref "KEY15") (pin "2") (pinfunction "2_2") (pintype "unspecified"))
      (node (ref "LIDAR-SLAVE") (pin "SDA0_A4_D18") (pinfunction "SDA0_A4_D18_SDA0_A4_D18") (pintype "bidirectional"))
    )
    (net (code "31") (name "Net-(KEY16-Pad1)") (class "Default")
      (node (ref "KEY16") (pin "1") (pinfunction "1_1") (pintype "unspecified"))
      (node (ref "R28") (pin "1") (pinfunction "1_1") (pintype "unspecified"))
    )
    (net (code "32") (name "Net-(KEY16-Pad2)") (class "Default")
      (node (ref "KEY16") (pin "2") (pinfunction "2_2") (pintype "unspecified"))
      (node (ref "LIDAR-SLAVE") (pin "SCL0_A5_D19") (pinfunction "SCL0_A5_D19_SCL0_A5_D19") (pintype "bidirectional"))
    )
    (net (code "33") (name "Net-(KEY17-Pad1)") (class "Default")
      (node (ref "KEY17") (pin "1") (pinfunction "1_1") (pintype "unspecified"))
      (node (ref "R31") (pin "1") (pinfunction "1_1") (pintype "unspecified"))
    )
    (net (code "34") (name "Net-(KEY17-Pad2)") (class "Default")
      (node (ref "KEY17") (pin "2") (pinfunction "2_2") (pintype "unspecified"))
      (node (ref "LIGHT-SLAVE") (pin "SDA0_A4_D18") (pinfunction "SDA0_A4_D18_SDA0_A4_D18") (pintype "bidirectional"))
    )
    (net (code "35") (name "Net-(KEY18-Pad1)") (class "Default")
      (node (ref "KEY18") (pin "1") (pinfunction "1_1") (pintype "unspecified"))
      (node (ref "R30") (pin "1") (pinfunction "1_1") (pintype "unspecified"))
    )
    (net (code "36") (name "Net-(KEY18-Pad2)") (class "Default")
      (node (ref "KEY18") (pin "2") (pinfunction "2_2") (pintype "unspecified"))
      (node (ref "LIGHT-SLAVE") (pin "SCL0_A5_D19") (pinfunction "SCL0_A5_D19_SCL0_A5_D19") (pintype "bidirectional"))
    )
    (net (code "37") (name "Net-(KEY19-Pad3)") (class "Default")
      (node (ref "KEY19") (pin "3") (pinfunction "3_3") (pintype "unspecified"))
      (node (ref "R36") (pin "2") (pinfunction "2_2") (pintype "unspecified"))
    )
    (net (code "38") (name "Net-(KEY19-Pad4)") (class "Default")
      (node (ref "KEY19") (pin "4") (pinfunction "4_4") (pintype "unspecified"))
      (node (ref "MAIN-MASTER") (pin "39/A20") (pinfunction "39/A20_39/A20") (pintype "bidirectional"))
    )
    (net (code "39") (name "Net-(LED33-A)") (class "Default")
      (node (ref "LED33") (pin "1") (pinfunction "A_1") (pintype "unspecified"))
      (node (ref "MAIN-MASTER") (pin "46") (pinfunction "SCK2/46_46") (pintype "bidirectional"))
    )
    (net (code "40") (name "Net-(LED33-C)") (class "Default")
      (node (ref "LED33") (pin "2") (pinfunction "C_2") (pintype "unspecified"))
      (node (ref "R14") (pin "2") (pinfunction "2_2") (pintype "unspecified"))
    )
    (net (code "41") (name "Net-(LED34-A)") (class "Default")
      (node (ref "LED34") (pin "1") (pinfunction "A_1") (pintype "unspecified"))
      (node (ref "MAIN-MASTER") (pin "49") (pinfunction "A23/49_49") (pintype "bidirectional"))
    )
    (net (code "42") (name "Net-(LED34-C)") (class "Default")
      (node (ref "LED34") (pin "2") (pinfunction "C_2") (pintype "unspecified"))
      (node (ref "R15") (pin "2") (pinfunction "2_2") (pintype "unspecified"))
    )
    (net (code "43") (name "Net-(LED35-A)") (class "Default")
      (node (ref "LED35") (pin "1") (pinfunction "A_1") (pintype "unspecified"))
      (node (ref "MAIN-MASTER") (pin "50") (pinfunction "A24/50_50") (pintype "bidirectional"))
    )
    (net (code "44") (name "Net-(LED35-C)") (class "Default")
      (node (ref "LED35") (pin "2") (pinfunction "C_2") (pintype "unspecified"))
      (node (ref "R16") (pin "2") (pinfunction "2_2") (pintype "unspecified"))
    )
    (net (code "45") (name "Net-(LED36-A)") (class "Default")
      (node (ref "LED36") (pin "1") (pinfunction "A_1") (pintype "unspecified"))
      (node (ref "MAIN-MASTER") (pin "51") (pinfunction "51_51") (pintype "bidirectional"))
    )
    (net (code "46") (name "Net-(LED36-C)") (class "Default")
      (node (ref "LED36") (pin "2") (pinfunction "C_2") (pintype "unspecified"))
      (node (ref "R17") (pin "2") (pinfunction "2_2") (pintype "unspecified"))
    )
    (net (code "47") (name "Net-(LED37-A)") (class "Default")
      (node (ref "LED37") (pin "1") (pinfunction "A_1") (pintype "unspecified"))
      (node (ref "MAIN-MASTER") (pin "52") (pinfunction "52_52") (pintype "bidirectional"))
    )
    (net (code "48") (name "Net-(LED37-C)") (class "Default")
      (node (ref "LED37") (pin "2") (pinfunction "C_2") (pintype "unspecified"))
      (node (ref "R18") (pin "2") (pinfunction "2_2") (pintype "unspecified"))
    )
    (net (code "49") (name "Net-(LED38-A)") (class "Default")
      (node (ref "LED38") (pin "1") (pinfunction "A_1") (pintype "unspecified"))
      (node (ref "MAIN-MASTER") (pin "53") (pinfunction "53_53") (pintype "bidirectional"))
    )
    (net (code "50") (name "Net-(LED38-C)") (class "Default")
      (node (ref "LED38") (pin "2") (pinfunction "C_2") (pintype "unspecified"))
      (node (ref "R19") (pin "2") (pinfunction "2_2") (pintype "unspecified"))
    )
    (net (code "51") (name "Net-(LED39-A)") (class "Default")
      (node (ref "LED39") (pin "1") (pinfunction "A_1") (pintype "unspecified"))
      (node (ref "MAIN-MASTER") (pin "45") (pinfunction "MISO2/45_45") (pintype "bidirectional"))
    )
    (net (code "52") (name "Net-(LED39-C)") (class "Default")
      (node (ref "LED39") (pin "2") (pinfunction "C_2") (pintype "unspecified"))
      (node (ref "R25") (pin "2") (pinfunction "2_2") (pintype "unspecified"))
    )
    (net (code "53") (name "Net-(LED40-A)") (class "Default")
      (node (ref "LED40") (pin "1") (pinfunction "A_1") (pintype "unspecified"))
      (node (ref "MAIN-MASTER") (pin "44") (pinfunction "MOSI2/44_44") (pintype "bidirectional"))
    )
    (net (code "54") (name "Net-(LED40-C)") (class "Default")
      (node (ref "LED40") (pin "2") (pinfunction "C_2") (pintype "unspecified"))
      (node (ref "R24") (pin "2") (pinfunction "2_2") (pintype "unspecified"))
    )
    (net (code "55") (name "Net-(LED41-A)") (class "Default")
      (node (ref "LED41") (pin "1") (pinfunction "A_1") (pintype "unspecified"))
      (node (ref "MAIN-MASTER") (pin "43") (pinfunction "43_43") (pintype "bidirectional"))
    )
    (net (code "56") (name "Net-(LED41-C)") (class "Default")
      (node (ref "LED41") (pin "2") (pinfunction "C_2") (pintype "unspecified"))
      (node (ref "R23") (pin "2") (pinfunction "2_2") (pintype "unspecified"))
    )
    (net (code "57") (name "Net-(LED42-A)") (class "Default")
      (node (ref "LED42") (pin "1") (pinfunction "A_1") (pintype "unspecified"))
      (node (ref "MAIN-MASTER") (pin "42") (pinfunction "42_42") (pintype "bidirectional"))
    )
    (net (code "58") (name "Net-(LED42-C)") (class "Default")
      (node (ref "LED42") (pin "2") (pinfunction "C_2") (pintype "unspecified"))
      (node (ref "R22") (pin "2") (pinfunction "2_2") (pintype "unspecified"))
    )
    (net (code "59") (name "Net-(LED43-A)") (class "Default")
      (node (ref "LED43") (pin "1") (pinfunction "A_1") (pintype "unspecified"))
      (node (ref "MAIN-MASTER") (pin "41") (pinfunction "41_41") (pintype "bidirectional"))
    )
    (net (code "60") (name "Net-(LED43-C)") (class "Default")
      (node (ref "LED43") (pin "2") (pinfunction "C_2") (pintype "unspecified"))
      (node (ref "R21") (pin "2") (pinfunction "2_2") (pintype "unspecified"))
    )
    (net (code "61") (name "Net-(LED44-A)") (class "Default")
      (node (ref "LED44") (pin "1") (pinfunction "A_1") (pintype "unspecified"))
      (node (ref "MAIN-MASTER") (pin "40") (pinfunction "40_40") (pintype "bidirectional"))
    )
    (net (code "62") (name "Net-(LED44-C)") (class "Default")
      (node (ref "LED44") (pin "2") (pinfunction "C_2") (pintype "unspecified"))
      (node (ref "R20") (pin "2") (pinfunction "2_2") (pintype "unspecified"))
    )
    (net (code "63") (name "Net-(LED45-A)") (class "Default")
      (node (ref "LED45") (pin "1") (pinfunction "A_1") (pintype "unspecified"))
      (node (ref "LIGHT-SLAVE") (pin "D2") (pinfunction "D2_D2") (pintype "bidirectional"))
    )
    (net (code "64") (name "Net-(LED45-C)") (class "Default")
      (node (ref "LED45") (pin "2") (pinfunction "C_2") (pintype "unspecified"))
      (node (ref "R32") (pin "2") (pinfunction "2_2") (pintype "unspecified"))
    )
    (net (code "65") (name "Net-(LED46-A)") (class "Default")
      (node (ref "LED46") (pin "1") (pinfunction "A_1") (pintype "unspecified"))
      (node (ref "LIGHT-SLAVE") (pin "D3") (pinfunction "D3_D3") (pintype "bidirectional"))
    )
    (net (code "66") (name "Net-(LED46-C)") (class "Default")
      (node (ref "LED46") (pin "2") (pinfunction "C_2") (pintype "unspecified"))
      (node (ref "R33") (pin "2") (pinfunction "2_2") (pintype "unspecified"))
    )
    (net (code "67") (name "Net-(LED47-A)") (class "Default")
      (node (ref "LED47") (pin "1") (pinfunction "A_1") (pintype "unspecified"))
      (node (ref "LIDAR-SLAVE") (pin "D3") (pinfunction "D3_D3") (pintype "bidirectional"))
    )
    (net (code "68") (name "Net-(LED47-C)") (class "Default")
      (node (ref "LED47") (pin "2") (pinfunction "C_2") (pintype "unspecified"))
      (node (ref "R34") (pin "2") (pinfunction "2_2") (pintype "unspecified"))
    )
    (net (code "69") (name "Net-(LED48-A)") (class "Default")
      (node (ref "LED48") (pin "1") (pinfunction "A_1") (pintype "unspecified"))
      (node (ref "LIDAR-SLAVE") (pin "D2") (pinfunction "D2_D2") (pintype "bidirectional"))
    )
    (net (code "70") (name "Net-(LED48-C)") (class "Default")
      (node (ref "LED48") (pin "2") (pinfunction "C_2") (pintype "unspecified"))
      (node (ref "R35") (pin "2") (pinfunction "2_2") (pintype "unspecified"))
    )
    (net (code "71") (name "Net-(LIDAR-SLAVE-D0{slash}RX1)") (class "Default")
      (node (ref "LIDAR-SLAVE") (pin "D0") (pinfunction "D0/RX1_D0") (pintype "bidirectional"))
      (node (ref "MAIN-MASTER") (pin "8") (pinfunction "8/TX3/PWM_8") (pintype "bidirectional"))
    )
    (net (code "72") (name "Net-(LIDAR-SLAVE-D1{slash}TX1)") (class "Default")
      (node (ref "LIDAR-SLAVE") (pin "D1") (pinfunction "D1/TX1_D1") (pintype "bidirectional"))
      (node (ref "MAIN-MASTER") (pin "7") (pinfunction "7/RX3/PWM_7") (pintype "bidirectional"))
    )
    (net (code "73") (name "Net-(LIDAR-SLAVE-D7{slash}RX2)") (class "Default")
      (node (ref "LIDAR-SLAVE") (pin "D7") (pinfunction "D7/RX2_D7") (pintype "bidirectional"))
      (node (ref "P1") (pin "4") (pinfunction "TX_4") (pintype "unspecified"))
    )
    (net (code "74") (name "Net-(LIDAR-SLAVE-D8{slash}TX1)") (class "Default")
      (node (ref "LIDAR-SLAVE") (pin "D8") (pinfunction "D8/TX1_D8") (pintype "bidirectional"))
      (node (ref "P1") (pin "3") (pinfunction "RX_3") (pintype "unspecified"))
    )
    (net (code "75") (name "Net-(LIDAR-SLAVE-PadA0_D14)") (class "Default")
      (node (ref "LIDAR-SLAVE") (pin "A0_D14") (pinfunction "A0_D14_A0_D14") (pintype "bidirectional"))
      (node (ref "LIGHT-SLAVE") (pin "A1_D15") (pinfunction "A1_D15_A1_D15") (pintype "bidirectional"))
    )
    (net (code "76") (name "Net-(LIDAR-SLAVE-PadA1_D15)") (class "Default")
      (node (ref "LIDAR-SLAVE") (pin "A1_D15") (pinfunction "A1_D15_A1_D15") (pintype "bidirectional"))
      (node (ref "LIGHT-SLAVE") (pin "A0_D14") (pinfunction "A0_D14_A0_D14") (pintype "bidirectional"))
    )
    (net (code "77") (name "Net-(LIDAR-SLAVE-PadD10)") (class "Default")
      (node (ref "LIDAR-SLAVE") (pin "D10") (pinfunction "D10_D10") (pintype "bidirectional"))
      (node (ref "MAIN-MASTER") (pin "24") (pinfunction "24_24") (pintype "bidirectional"))
    )
    (net (code "78") (name "Net-(LIGHT-SLAVE-D0{slash}RX1)") (class "Default")
      (node (ref "LIGHT-SLAVE") (pin "D0") (pinfunction "D0/RX1_D0") (pintype "bidirectional"))
      (node (ref "MAIN-MASTER") (pin "1") (pinfunction "1/TX1/MISO1_1") (pintype "bidirectional"))
    )
    (net (code "79") (name "Net-(LIGHT-SLAVE-D1{slash}TX1)") (class "Default")
      (node (ref "LIGHT-SLAVE") (pin "D1") (pinfunction "D1/TX1_D1") (pintype "bidirectional"))
      (node (ref "MAIN-MASTER") (pin "0") (pinfunction "0/RX1/MOSI1_0") (pintype "bidirectional"))
    )
    (net (code "80") (name "Net-(MAIN-MASTER-6{slash}PWM)") (class "Default")
      (node (ref "LIGHT-SLAVE") (pin "D12") (pinfunction "D12_D12") (pintype "bidirectional"))
      (node (ref "MAIN-MASTER") (pin "6") (pinfunction "6/PWM_6") (pintype "bidirectional"))
    )
    (net (code "81") (name "Net-(MAIN-MASTER-11{slash}MOSI0)") (class "Default")
      (node (ref "LIGHT-SLAVE") (pin "D11") (pinfunction "D11_D11") (pintype "bidirectional"))
      (node (ref "MAIN-MASTER") (pin "11") (pinfunction "11/MOSI0_11") (pintype "bidirectional"))
    )
    (net (code "82") (name "Net-(MAIN-MASTER-12{slash}MISO0)") (class "Default")
      (node (ref "LIGHT-SLAVE") (pin "D10") (pinfunction "D10_D10") (pintype "bidirectional"))
      (node (ref "MAIN-MASTER") (pin "12") (pinfunction "12/MISO0_12") (pintype "bidirectional"))
    )
    (net (code "83") (name "Net-(MAIN-MASTER-14{slash}A0{slash}PWM)") (class "Default")
      (node (ref "MAIN-MASTER") (pin "14/A0") (pinfunction "14/A0/PWM_14/A0") (pintype "bidirectional"))
      (node (ref "P2") (pin "1") (pinfunction "1_1") (pintype "input"))
    )
    (net (code "84") (name "Net-(MAIN-MASTER-18{slash}A4{slash}SDA0)") (class "Default")
      (node (ref "J7") (pin "2") (pinfunction "2_2") (pintype "unspecified"))
      (node (ref "MAIN-MASTER") (pin "18/A4") (pinfunction "18/A4/SDA0_18/A4") (pintype "bidirectional"))
    )
    (net (code "85") (name "Net-(MAIN-MASTER-19{slash}A5{slash}SCL0)") (class "Default")
      (node (ref "J7") (pin "1") (pinfunction "1_1") (pintype "unspecified"))
      (node (ref "MAIN-MASTER") (pin "19/A5") (pinfunction "19/A5/SCL0_19/A5") (pintype "bidirectional"))
    )
    (net (code "86") (name "Net-(MAIN-MASTER-20{slash}A6{slash}PWM)") (class "Default")
      (node (ref "MAIN-MASTER") (pin "20/A6") (pinfunction "20/A6/PWM_20/A6") (pintype "bidirectional"))
      (node (ref "P6") (pin "1") (pinfunction "1_1") (pintype "input"))
    )
    (net (code "87") (name "Net-(MAIN-MASTER-21{slash}A7{slash}PWM)") (class "Default")
      (node (ref "MAIN-MASTER") (pin "21/A7") (pinfunction "21/A7/PWM_21/A7") (pintype "bidirectional"))
      (node (ref "P7") (pin "1") (pinfunction "1_1") (pintype "input"))
    )
    (net (code "88") (name "Net-(MAIN-MASTER-22{slash}A8{slash}PWM)") (class "Default")
      (node (ref "MAIN-MASTER") (pin "22/A8") (pinfunction "22/A8/PWM_22/A8") (pintype "bidirectional"))
      (node (ref "P9") (pin "1") (pinfunction "1_1") (pintype "input"))
    )
    (net (code "89") (name "Net-(MAIN-MASTER-23{slash}A9{slash}PWM)") (class "Default")
      (node (ref "LIDAR-SLAVE") (pin "D9") (pinfunction "D9_D9") (pintype "bidirectional"))
      (node (ref "MAIN-MASTER") (pin "23/A9") (pinfunction "23/A9/PWM_23/A9") (pintype "bidirectional"))
    )
    (net (code "90") (name "Net-(MAIN-MASTER-29{slash}PWM)") (class "Default")
      (node (ref "MAIN-MASTER") (pin "29") (pinfunction "29/PWM_29") (pintype "bidirectional"))
      (node (ref "P11") (pin "1") (pinfunction "1_1") (pintype "input"))
    )
    (net (code "91") (name "Net-(MAIN-MASTER-30{slash}PWM)") (class "Default")
      (node (ref "MAIN-MASTER") (pin "30") (pinfunction "30/PWM_30") (pintype "bidirectional"))
      (node (ref "P10") (pin "1") (pinfunction "1_1") (pintype "input"))
    )
    (net (code "92") (name "Net-(MAIN-MASTER-33{slash}A14{slash}TX5)") (class "Default")
      (node (ref "J5") (pin "2") (pinfunction "2_2") (pintype "unspecified"))
      (node (ref "MAIN-MASTER") (pin "33/A14") (pinfunction "33/A14/TX5_33/A14") (pintype "bidirectional"))
    )
    (net (code "93") (name "Net-(MAIN-MASTER-34{slash}A15{slash}RX5)") (class "Default")
      (node (ref "J5") (pin "1") (pinfunction "1_1") (pintype "unspecified"))
      (node (ref "MAIN-MASTER") (pin "34/A15") (pinfunction "34/A15/RX5_34/A15") (pintype "bidirectional"))
    )
    (net (code "94") (name "Net-(MAIN-MASTER-35{slash}A16{slash}PWM)") (class "Default")
      (node (ref "MAIN-MASTER") (pin "35/A16") (pinfunction "35/A16/PWM_35/A16") (pintype "bidirectional"))
      (node (ref "MULTI17-1") (pin "1") (pinfunction "COMMON_INOUT/OUTPUT_1") (pintype "unspecified"))
    )
    (net (code "95") (name "Net-(MAIN-MASTER-36{slash}A17{slash}PWM)") (class "Default")
      (node (ref "MAIN-MASTER") (pin "36/A17") (pinfunction "36/A17/PWM_36/A17") (pintype "bidirectional"))
      (node (ref "MULTI17-1") (pin "15") (pinfunction "E#_15") (pintype "unspecified"))
    )
    (net (code "96") (name "Net-(MAIN-MASTER-37{slash}A18{slash}SCL1{slash}PWM)") (class "Default")
      (node (ref "J6") (pin "2") (pinfunction "2_2") (pintype "unspecified"))
      (node (ref "MAIN-MASTER") (pin "37/A18") (pinfunction "37/A18/SCL1/PWM_37/A18") (pintype "bidirectional"))
    )
    (net (code "97") (name "Net-(MAIN-MASTER-38{slash}A19{slash}SDA1{slash}PWM)") (class "Default")
      (node (ref "J6") (pin "1") (pinfunction "1_1") (pintype "unspecified"))
      (node (ref "MAIN-MASTER") (pin "38/A19") (pinfunction "38/A19/SDA1/PWM_38/A19") (pintype "bidirectional"))
    )
    (net (code "98") (name "Net-(MAIN-MASTER-Pad15{slash}A1)") (class "Default")
      (node (ref "MAIN-MASTER") (pin "15/A1") (pinfunction "15/A1_15/A1") (pintype "bidirectional"))
      (node (ref "P3") (pin "1") (pinfunction "1_1") (pintype "input"))
    )
    (net (code "99") (name "Net-(MULTI17-1-I0)") (class "Default")
      (node (ref "KEY1") (pin "1") (pinfunction "1_1") (pintype "unspecified"))
      (node (ref "MULTI17-1") (pin "9") (pinfunction "I0_9") (pintype "unspecified"))
    )
    (net (code "100") (name "Net-(MULTI17-1-I1)") (class "Default")
      (node (ref "KEY2") (pin "1") (pinfunction "1_1") (pintype "unspecified"))
      (node (ref "MULTI17-1") (pin "8") (pinfunction "I1_8") (pintype "unspecified"))
    )
    (net (code "101") (name "Net-(MULTI17-1-I2)") (class "Default")
      (node (ref "KEY3") (pin "1") (pinfunction "1_1") (pintype "unspecified"))
      (node (ref "MULTI17-1") (pin "7") (pinfunction "I2_7") (pintype "unspecified"))
    )
    (net (code "102") (name "Net-(MULTI17-1-I3)") (class "Default")
      (node (ref "KEY4") (pin "1") (pinfunction "1_1") (pintype "unspecified"))
      (node (ref "MULTI17-1") (pin "6") (pinfunction "I3_6") (pintype "unspecified"))
    )
    (net (code "103") (name "Net-(MULTI17-1-I4)") (class "Default")
      (node (ref "KEY5") (pin "1") (pinfunction "1_1") (pintype "unspecified"))
      (node (ref "MULTI17-1") (pin "5") (pinfunction "I4_5") (pintype "unspecified"))
    )
    (net (code "104") (name "Net-(MULTI17-1-I5)") (class "Default")
      (node (ref "KEY6") (pin "1") (pinfunction "1_1") (pintype "unspecified"))
      (node (ref "MULTI17-1") (pin "4") (pinfunction "I5_4") (pintype "unspecified"))
    )
    (net (code "105") (name "Net-(MULTI17-1-I8)") (class "Default")
      (node (ref "KEY7") (pin "2") (pinfunction "2_2") (pintype "unspecified"))
      (node (ref "MULTI17-1") (pin "23") (pinfunction "I8_23") (pintype "unspecified"))
    )
    (net (code "106") (name "Net-(MULTI17-1-I9)") (class "Default")
      (node (ref "KEY8") (pin "2") (pinfunction "2_2") (pintype "unspecified"))
      (node (ref "MULTI17-1") (pin "22") (pinfunction "I9_22") (pintype "unspecified"))
    )
    (net (code "107") (name "Net-(MULTI17-1-I10)") (class "Default")
      (node (ref "KEY9") (pin "2") (pinfunction "2_2") (pintype "unspecified"))
      (node (ref "MULTI17-1") (pin "21") (pinfunction "I10_21") (pintype "unspecified"))
    )
    (net (code "108") (name "Net-(MULTI17-1-I11)") (class "Default")
      (node (ref "KEY10") (pin "2") (pinfunction "2_2") (pintype "unspecified"))
      (node (ref "MULTI17-1") (pin "20") (pinfunction "I11_20") (pintype "unspecified"))
    )
    (net (code "109") (name "Net-(MULTI17-1-I12)") (class "Default")
      (node (ref "KEY11") (pin "2") (pinfunction "2_2") (pintype "unspecified"))
      (node (ref "MULTI17-1") (pin "19") (pinfunction "I12_19") (pintype "unspecified"))
    )
    (net (code "110") (name "Net-(MULTI17-1-I13)") (class "Default")
      (node (ref "KEY12") (pin "2") (pinfunction "2_2") (pintype "unspecified"))
      (node (ref "MULTI17-1") (pin "18") (pinfunction "I13_18") (pintype "unspecified"))
    )
    (net (code "111") (name "Net-(MULTI17-1-S0)") (class "Default")
      (node (ref "MAIN-MASTER") (pin "57") (pinfunction "57_57") (pintype "bidirectional"))
      (node (ref "MULTI17-1") (pin "10") (pinfunction "S0_10") (pintype "unspecified"))
    )
    (net (code "112") (name "Net-(MULTI17-1-S1)") (class "Default")
      (node (ref "MAIN-MASTER") (pin "56") (pinfunction "56_56") (pintype "bidirectional"))
      (node (ref "MULTI17-1") (pin "11") (pinfunction "S1_11") (pintype "unspecified"))
    )
    (net (code "113") (name "Net-(MULTI17-1-S2)") (class "Default")
      (node (ref "MAIN-MASTER") (pin "54") (pinfunction "54_54") (pintype "bidirectional"))
      (node (ref "MULTI17-1") (pin "14") (pinfunction "S2_14") (pintype "unspecified"))
    )
    (net (code "114") (name "Net-(MULTI17-1-S3)") (class "Default")
      (node (ref "MAIN-MASTER") (pin "55") (pinfunction "55_55") (pintype "bidirectional"))
      (node (ref "MULTI17-1") (pin "13") (pinfunction "S3_13") (pintype "unspecified"))
    )
    (net (code "115") (name "Net-(P1-MCTRL)") (class "Default")
      (node (ref "LIDAR-SLAVE") (pin "SCL1_A2_D16") (pinfunction "SCL1_A2_D16_SCL1_A2_D16") (pintype "bidirectional"))
      (node (ref "P1") (pin "1") (pinfunction "MCTRL_1") (pintype "unspecified"))
    )
    (net (code "116") (name "Net-(U1-INPUT)") (class "Default")
      (node (ref "J8") (pin "2") (pinfunction "2_2") (pintype "unspecified"))
      (node (ref "U1") (pin "1") (pinfunction "INPUT_1") (pintype "unspecified"))
    )
    (net (code "117") (name "VCC") (class "Default")
      (node (ref "KEY19") (pin "1") (pinfunction "1_1") (pintype "unspecified"))
      (node (ref "MAIN-MASTER") (pin "3.3V") (pinfunction "3.3V_3.3V") (pintype "bidirectional"))
      (node (ref "MAIN-MASTER") (pin "3.3V2") (pinfunction "3.3V_3.3V2") (pintype "bidirectional"))
      (node (ref "MAIN-MASTER") (pin "3.3V3") (pinfunction "3.3V_3.3V3") (pintype "bidirectional"))
      (node (ref "MAIN-MASTER") (pin "3.3V4") (pinfunction "3.3V_3.3V4") (pintype "bidirectional"))
      (node (ref "MULTI17-1") (pin "24") (pinfunction "VCC_24") (pintype "unspecified"))
    )
    (net (code "118") (name "unconnected-(HC05/HM1-EN-Pad6)") (class "Default")
      (node (ref "HC05/HM1") (pin "6") (pinfunction "EN_6") (pintype "unspecified+no_connect"))
    )
    (net (code "119") (name "unconnected-(HC05/HM1-State-Pad1)") (class "Default")
      (node (ref "HC05/HM1") (pin "1") (pinfunction "State_1") (pintype "unspecified+no_connect"))
    )
    (net (code "120") (name "unconnected-(IMU-ADD-Pad5)") (class "Default")
      (node (ref "IMU") (pin "5") (pinfunction "ADD_5") (pintype "unspecified+no_connect"))
    )
    (net (code "121") (name "unconnected-(IMU-BOOT-Pad7)") (class "Default")
      (node (ref "IMU") (pin "7") (pinfunction "BOOT_7") (pintype "unspecified+no_connect"))
    )
    (net (code "122") (name "unconnected-(IMU-INT-Pad6)") (class "Default")
      (node (ref "IMU") (pin "6") (pinfunction "INT_6") (pintype "unspecified+no_connect"))
    )
    (net (code "123") (name "unconnected-(IMU-REST-Pad8)") (class "Default")
      (node (ref "IMU") (pin "8") (pinfunction "REST_8") (pintype "unspecified+no_connect"))
    )
    (net (code "124") (name "unconnected-(KEY1-Pad2)") (class "Default")
      (node (ref "KEY1") (pin "2") (pinfunction "2_2") (pintype "unspecified+no_connect"))
    )
    (net (code "125") (name "unconnected-(KEY1-Pad3)") (class "Default")
      (node (ref "KEY1") (pin "3") (pinfunction "3_3") (pintype "unspecified+no_connect"))
    )
    (net (code "126") (name "unconnected-(KEY2-Pad2)") (class "Default")
      (node (ref "KEY2") (pin "2") (pinfunction "2_2") (pintype "unspecified+no_connect"))
    )
    (net (code "127") (name "unconnected-(KEY2-Pad3)") (class "Default")
      (node (ref "KEY2") (pin "3") (pinfunction "3_3") (pintype "unspecified+no_connect"))
    )
    (net (code "128") (name "unconnected-(KEY3-Pad2)") (class "Default")
      (node (ref "KEY3") (pin "2") (pinfunction "2_2") (pintype "unspecified+no_connect"))
    )
    (net (code "129") (name "unconnected-(KEY3-Pad3)") (class "Default")
      (node (ref "KEY3") (pin "3") (pinfunction "3_3") (pintype "unspecified+no_connect"))
    )
    (net (code "130") (name "unconnected-(KEY4-Pad2)") (class "Default")
      (node (ref "KEY4") (pin "2") (pinfunction "2_2") (pintype "unspecified+no_connect"))
    )
    (net (code "131") (name "unconnected-(KEY4-Pad3)") (class "Default")
      (node (ref "KEY4") (pin "3") (pinfunction "3_3") (pintype "unspecified+no_connect"))
    )
    (net (code "132") (name "unconnected-(KEY5-Pad2)") (class "Default")
      (node (ref "KEY5") (pin "2") (pinfunction "2_2") (pintype "unspecified+no_connect"))
    )
    (net (code "133") (name "unconnected-(KEY5-Pad3)") (class "Default")
      (node (ref "KEY5") (pin "3") (pinfunction "3_3") (pintype "unspecified+no_connect"))
    )
    (net (code "134") (name "unconnected-(KEY6-Pad2)") (class "Default")
      (node (ref "KEY6") (pin "2") (pinfunction "2_2") (pintype "unspecified+no_connect"))
    )
    (net (code "135") (name "unconnected-(KEY6-Pad3)") (class "Default")
      (node (ref "KEY6") (pin "3") (pinfunction "3_3") (pintype "unspecified+no_connect"))
    )
    (net (code "136") (name "unconnected-(KEY7-Pad1)") (class "Default")
      (node (ref "KEY7") (pin "1") (pinfunction "1_1") (pintype "unspecified+no_connect"))
    )
    (net (code "137") (name "unconnected-(KEY7-Pad4)") (class "Default")
      (node (ref "KEY7") (pin "4") (pinfunction "4_4") (pintype "unspecified+no_connect"))
    )
    (net (code "138") (name "unconnected-(KEY8-Pad1)") (class "Default")
      (node (ref "KEY8") (pin "1") (pinfunction "1_1") (pintype "unspecified+no_connect"))
    )
    (net (code "139") (name "unconnected-(KEY8-Pad4)") (class "Default")
      (node (ref "KEY8") (pin "4") (pinfunction "4_4") (pintype "unspecified+no_connect"))
    )
    (net (code "140") (name "unconnected-(KEY9-Pad1)") (class "Default")
      (node (ref "KEY9") (pin "1") (pinfunction "1_1") (pintype "unspecified+no_connect"))
    )
    (net (code "141") (name "unconnected-(KEY9-Pad4)") (class "Default")
      (node (ref "KEY9") (pin "4") (pinfunction "4_4") (pintype "unspecified+no_connect"))
    )
    (net (code "142") (name "unconnected-(KEY10-Pad1)") (class "Default")
      (node (ref "KEY10") (pin "1") (pinfunction "1_1") (pintype "unspecified+no_connect"))
    )
    (net (code "143") (name "unconnected-(KEY10-Pad4)") (class "Default")
      (node (ref "KEY10") (pin "4") (pinfunction "4_4") (pintype "unspecified+no_connect"))
    )
    (net (code "144") (name "unconnected-(KEY11-Pad1)") (class "Default")
      (node (ref "KEY11") (pin "1") (pinfunction "1_1") (pintype "unspecified+no_connect"))
    )
    (net (code "145") (name "unconnected-(KEY11-Pad4)") (class "Default")
      (node (ref "KEY11") (pin "4") (pinfunction "4_4") (pintype "unspecified+no_connect"))
    )
    (net (code "146") (name "unconnected-(KEY12-Pad1)") (class "Default")
      (node (ref "KEY12") (pin "1") (pinfunction "1_1") (pintype "unspecified+no_connect"))
    )
    (net (code "147") (name "unconnected-(KEY12-Pad4)") (class "Default")
      (node (ref "KEY12") (pin "4") (pinfunction "4_4") (pintype "unspecified+no_connect"))
    )
    (net (code "148") (name "unconnected-(KEY15-Pad4)") (class "Default")
      (node (ref "KEY15") (pin "4") (pinfunction "4_4") (pintype "unspecified+no_connect"))
    )
    (net (code "149") (name "unconnected-(KEY16-Pad4)") (class "Default")
      (node (ref "KEY16") (pin "4") (pinfunction "4_4") (pintype "unspecified+no_connect"))
    )
    (net (code "150") (name "unconnected-(KEY17-Pad4)") (class "Default")
      (node (ref "KEY17") (pin "4") (pinfunction "4_4") (pintype "unspecified+no_connect"))
    )
    (net (code "151") (name "unconnected-(KEY18-Pad4)") (class "Default")
      (node (ref "KEY18") (pin "4") (pinfunction "4_4") (pintype "unspecified+no_connect"))
    )
    (net (code "152") (name "unconnected-(KEY19-Pad2)") (class "Default")
      (node (ref "KEY19") (pin "2") (pinfunction "2_2") (pintype "unspecified+no_connect"))
    )
    (net (code "153") (name "unconnected-(LIDAR-SLAVE-Pad3.3V)") (class "Default")
      (node (ref "LIDAR-SLAVE") (pin "3.3V") (pinfunction "3.3V_3.3V") (pintype "bidirectional+no_connect"))
    )
    (net (code "154") (name "unconnected-(LIDAR-SLAVE-Pad3.3V)_1") (class "Default")
      (node (ref "LIDAR-SLAVE") (pin "3.3V") (pinfunction "3.3V_3.3V") (pintype "input+no_connect"))
    )
    (net (code "155") (name "unconnected-(LIDAR-SLAVE-PadA6_D20)") (class "Default")
      (node (ref "LIDAR-SLAVE") (pin "A6_D20") (pinfunction "A6_D20_A6_D20") (pintype "bidirectional+no_connect"))
    )
    (net (code "156") (name "unconnected-(LIDAR-SLAVE-PadA7_D21)") (class "Default")
      (node (ref "LIDAR-SLAVE") (pin "A7_D21") (pinfunction "A7_D21_A7_D21") (pintype "bidirectional+no_connect"))
    )
    (net (code "157") (name "unconnected-(LIDAR-SLAVE-PadA8_D22)") (class "Default")
      (node (ref "LIDAR-SLAVE") (pin "A8_D22") (pinfunction "A8_D22_A8_D22") (pintype "bidirectional+no_connect"))
    )
    (net (code "158") (name "unconnected-(LIDAR-SLAVE-PadA9_D23)") (class "Default")
      (node (ref "LIDAR-SLAVE") (pin "A9_D23") (pinfunction "A9_D23_A9_D23") (pintype "bidirectional+no_connect"))
    )
    (net (code "159") (name "unconnected-(LIDAR-SLAVE-PadA13_D27)") (class "Default")
      (node (ref "LIDAR-SLAVE") (pin "A13_D27") (pinfunction "A13_D27_A13_D27") (pintype "bidirectional+no_connect"))
    )
    (net (code "160") (name "unconnected-(LIDAR-SLAVE-PadD4)") (class "Default")
      (node (ref "LIDAR-SLAVE") (pin "D4") (pinfunction "D4_D4") (pintype "bidirectional+no_connect"))
    )
    (net (code "161") (name "unconnected-(LIDAR-SLAVE-PadD5)") (class "Default")
      (node (ref "LIDAR-SLAVE") (pin "D5") (pinfunction "D5_D5") (pintype "bidirectional+no_connect"))
    )
    (net (code "162") (name "unconnected-(LIDAR-SLAVE-PadD6)") (class "Default")
      (node (ref "LIDAR-SLAVE") (pin "D6") (pinfunction "D6_D6") (pintype "bidirectional+no_connect"))
    )
    (net (code "163") (name "unconnected-(LIDAR-SLAVE-PadD11)") (class "Default")
      (node (ref "LIDAR-SLAVE") (pin "D11") (pinfunction "D11_D11") (pintype "bidirectional+no_connect"))
    )
    (net (code "164") (name "unconnected-(LIDAR-SLAVE-PadD12)") (class "Default")
      (node (ref "LIDAR-SLAVE") (pin "D12") (pinfunction "D12_D12") (pintype "bidirectional+no_connect"))
    )
    (net (code "165") (name "unconnected-(LIDAR-SLAVE-PadD24_A10_SCL2)") (class "Default")
      (node (ref "LIDAR-SLAVE") (pin "D24_A10_SCL2") (pinfunction "D24_A10_SCL2_D24_A10_SCL2") (pintype "bidirectional+no_connect"))
    )
    (net (code "166") (name "unconnected-(LIDAR-SLAVE-PadD26_A12)") (class "Default")
      (node (ref "LIDAR-SLAVE") (pin "D26_A12") (pinfunction "D26_A12_D26_A12") (pintype "bidirectional+no_connect"))
    )
    (net (code "167") (name "unconnected-(LIDAR-SLAVE-PadD28)") (class "Default")
      (node (ref "LIDAR-SLAVE") (pin "D28") (pinfunction "D28_D28") (pintype "bidirectional+no_connect"))
    )
    (net (code "168") (name "unconnected-(LIDAR-SLAVE-PadD29)") (class "Default")
      (node (ref "LIDAR-SLAVE") (pin "D29") (pinfunction "D29_D29") (pintype "bidirectional+no_connect"))
    )
    (net (code "169") (name "unconnected-(LIDAR-SLAVE-PadD30)") (class "Default")
      (node (ref "LIDAR-SLAVE") (pin "D30") (pinfunction "D30_D30") (pintype "bidirectional+no_connect"))
    )
    (net (code "170") (name "unconnected-(LIDAR-SLAVE-PadD31)") (class "Default")
      (node (ref "LIDAR-SLAVE") (pin "D31") (pinfunction "D31_D31") (pintype "bidirectional+no_connect"))
    )
    (net (code "171") (name "unconnected-(LIDAR-SLAVE-PadD32)") (class "Default")
      (node (ref "LIDAR-SLAVE") (pin "D32") (pinfunction "D32_D32") (pintype "bidirectional+no_connect"))
    )
    (net (code "172") (name "unconnected-(LIDAR-SLAVE-PadD33)") (class "Default")
      (node (ref "LIDAR-SLAVE") (pin "D33") (pinfunction "D33_D33") (pintype "bidirectional+no_connect"))
    )
    (net (code "173") (name "unconnected-(LIDAR-SLAVE-PadGND)") (class "Default")
      (node (ref "LIDAR-SLAVE") (pin "GND") (pinfunction "GND_GND") (pintype "passive+no_connect"))
    )
    (net (code "174") (name "unconnected-(LIDAR-SLAVE-PadGND)_1") (class "Default")
      (node (ref "LIDAR-SLAVE") (pin "GND") (pinfunction "GND_GND") (pintype "input+no_connect"))
    )
    (net (code "175") (name "unconnected-(LIDAR-SLAVE-PadLED_D13)") (class "Default")
      (node (ref "LIDAR-SLAVE") (pin "LED_D13") (pinfunction "LED_D13_LED_D13") (pintype "bidirectional+no_connect"))
    )
    (net (code "176") (name "unconnected-(LIDAR-SLAVE-PadOnOff)") (class "Default")
      (node (ref "LIDAR-SLAVE") (pin "OnOff") (pinfunction "OnOff_OnOff") (pintype "input+no_connect"))
    )
    (net (code "177") (name "unconnected-(LIDAR-SLAVE-PadProgram)") (class "Default")
      (node (ref "LIDAR-SLAVE") (pin "Program") (pinfunction "Program_Program") (pintype "input+no_connect"))
    )
    (net (code "178") (name "unconnected-(LIDAR-SLAVE-PadSDA1_A3_D17)") (class "Default")
      (node (ref "LIDAR-SLAVE") (pin "SDA1_A3_D17") (pinfunction "SDA1_A3_D17_SDA1_A3_D17") (pintype "bidirectional+no_connect"))
    )
    (net (code "179") (name "unconnected-(LIDAR-SLAVE-PadSDA2_A11_D25)") (class "Default")
      (node (ref "LIDAR-SLAVE") (pin "SDA2_A11_D25") (pinfunction "SDA2_A11_D25_SDA2_A11_D25") (pintype "bidirectional+no_connect"))
    )
    (net (code "180") (name "unconnected-(LIDAR-SLAVE-PadVBat)") (class "Default")
      (node (ref "LIDAR-SLAVE") (pin "VBat") (pinfunction "VBat_VBat") (pintype "input+no_connect"))
    )
    (net (code "181") (name "unconnected-(LIDAR-SLAVE-PadVusb)") (class "Default")
      (node (ref "LIDAR-SLAVE") (pin "Vusb") (pinfunction "Vusb_Vusb") (pintype "passive+no_connect"))
    )
    (net (code "182") (name "unconnected-(LIGHT-SLAVE-Pad3.3V)") (class "Default")
      (node (ref "LIGHT-SLAVE") (pin "3.3V") (pinfunction "3.3V_3.3V") (pintype "input+no_connect"))
    )
    (net (code "183") (name "unconnected-(LIGHT-SLAVE-PadA13_D27)") (class "Default")
      (node (ref "LIGHT-SLAVE") (pin "A13_D27") (pinfunction "A13_D27_A13_D27") (pintype "bidirectional+no_connect"))
    )
    (net (code "184") (name "unconnected-(LIGHT-SLAVE-PadD4)") (class "Default")
      (node (ref "LIGHT-SLAVE") (pin "D4") (pinfunction "D4_D4") (pintype "bidirectional+no_connect"))
    )
    (net (code "185") (name "unconnected-(LIGHT-SLAVE-PadD5)") (class "Default")
      (node (ref "LIGHT-SLAVE") (pin "D5") (pinfunction "D5_D5") (pintype "bidirectional+no_connect"))
    )
    (net (code "186") (name "unconnected-(LIGHT-SLAVE-PadD6)") (class "Default")
      (node (ref "LIGHT-SLAVE") (pin "D6") (pinfunction "D6_D6") (pintype "bidirectional+no_connect"))
    )
    (net (code "187") (name "unconnected-(LIGHT-SLAVE-PadD7)") (class "Default")
      (node (ref "LIGHT-SLAVE") (pin "D7") (pinfunction "D7_D7") (pintype "bidirectional+no_connect"))
    )
    (net (code "188") (name "unconnected-(LIGHT-SLAVE-PadD8)") (class "Default")
      (node (ref "LIGHT-SLAVE") (pin "D8") (pinfunction "D8_D8") (pintype "bidirectional+no_connect"))
    )
    (net (code "189") (name "unconnected-(LIGHT-SLAVE-PadD24_A10_SCL2)") (class "Default")
      (node (ref "LIGHT-SLAVE") (pin "D24_A10_SCL2") (pinfunction "D24_A10_SCL2_D24_A10_SCL2") (pintype "bidirectional+no_connect"))
    )
    (net (code "190") (name "unconnected-(LIGHT-SLAVE-PadD26_A12)") (class "Default")
      (node (ref "LIGHT-SLAVE") (pin "D26_A12") (pinfunction "D26_A12_D26_A12") (pintype "bidirectional+no_connect"))
    )
    (net (code "191") (name "unconnected-(LIGHT-SLAVE-PadD28)") (class "Default")
      (node (ref "LIGHT-SLAVE") (pin "D28") (pinfunction "D28_D28") (pintype "bidirectional+no_connect"))
    )
    (net (code "192") (name "unconnected-(LIGHT-SLAVE-PadD29)") (class "Default")
      (node (ref "LIGHT-SLAVE") (pin "D29") (pinfunction "D29_D29") (pintype "bidirectional+no_connect"))
    )
    (net (code "193") (name "unconnected-(LIGHT-SLAVE-PadD30)") (class "Default")
      (node (ref "LIGHT-SLAVE") (pin "D30") (pinfunction "D30_D30") (pintype "bidirectional+no_connect"))
    )
    (net (code "194") (name "unconnected-(LIGHT-SLAVE-PadD31)") (class "Default")
      (node (ref "LIGHT-SLAVE") (pin "D31") (pinfunction "D31_D31") (pintype "bidirectional+no_connect"))
    )
    (net (code "195") (name "unconnected-(LIGHT-SLAVE-PadD32)") (class "Default")
      (node (ref "LIGHT-SLAVE") (pin "D32") (pinfunction "D32_D32") (pintype "bidirectional+no_connect"))
    )
    (net (code "196") (name "unconnected-(LIGHT-SLAVE-PadD33)") (class "Default")
      (node (ref "LIGHT-SLAVE") (pin "D33") (pinfunction "D33_D33") (pintype "bidirectional+no_connect"))
    )
    (net (code "197") (name "unconnected-(LIGHT-SLAVE-PadGND)") (class "Default")
      (node (ref "LIGHT-SLAVE") (pin "GND") (pinfunction "GND_GND") (pintype "passive+no_connect"))
    )
    (net (code "198") (name "unconnected-(LIGHT-SLAVE-PadGND)_1") (class "Default")
      (node (ref "LIGHT-SLAVE") (pin "GND") (pinfunction "GND_GND") (pintype "input+no_connect"))
    )
    (net (code "199") (name "unconnected-(LIGHT-SLAVE-PadLED_D13)") (class "Default")
      (node (ref "LIGHT-SLAVE") (pin "LED_D13") (pinfunction "LED_D13_LED_D13") (pintype "bidirectional+no_connect"))
    )
    (net (code "200") (name "unconnected-(LIGHT-SLAVE-PadOnOff)") (class "Default")
      (node (ref "LIGHT-SLAVE") (pin "OnOff") (pinfunction "OnOff_OnOff") (pintype "input+no_connect"))
    )
    (net (code "201") (name "unconnected-(LIGHT-SLAVE-PadProgram)") (class "Default")
      (node (ref "LIGHT-SLAVE") (pin "Program") (pinfunction "Program_Program") (pintype "input+no_connect"))
    )
    (net (code "202") (name "unconnected-(LIGHT-SLAVE-PadSDA2_A11_D25)") (class "Default")
      (node (ref "LIGHT-SLAVE") (pin "SDA2_A11_D25") (pinfunction "SDA2_A11_D25_SDA2_A11_D25") (pintype "bidirectional+no_connect"))
    )
    (net (code "203") (name "unconnected-(LIGHT-SLAVE-PadVBat)") (class "Default")
      (node (ref "LIGHT-SLAVE") (pin "VBat") (pinfunction "VBat_VBat") (pintype "input+no_connect"))
    )
    (net (code "204") (name "unconnected-(LIGHT-SLAVE-PadVusb)") (class "Default")
      (node (ref "LIGHT-SLAVE") (pin "Vusb") (pinfunction "Vusb_Vusb") (pintype "passive+no_connect"))
    )
    (net (code "205") (name "unconnected-(MAIN-MASTER-13{slash}SCK0{slash}LED-Pad13)") (class "Default")
      (node (ref "MAIN-MASTER") (pin "13") (pinfunction "13/SCK0/LED_13") (pintype "bidirectional+no_connect"))
    )
    (net (code "206") (name "unconnected-(MAIN-MASTER-PadA10)") (class "Default")
      (node (ref "MAIN-MASTER") (pin "A10") (pinfunction "A10_A10") (pintype "bidirectional+no_connect"))
    )
    (net (code "207") (name "unconnected-(MAIN-MASTER-PadA11)") (class "Default")
      (node (ref "MAIN-MASTER") (pin "A11") (pinfunction "A11_A11") (pintype "bidirectional+no_connect"))
    )
    (net (code "208") (name "unconnected-(MAIN-MASTER-PadA25)") (class "Default")
      (node (ref "MAIN-MASTER") (pin "A25") (pinfunction "A25_A25") (pintype "bidirectional+no_connect"))
    )
    (net (code "209") (name "unconnected-(MAIN-MASTER-PadA26)") (class "Default")
      (node (ref "MAIN-MASTER") (pin "A26") (pinfunction "A26_A26") (pintype "bidirectional+no_connect"))
    )
    (net (code "210") (name "unconnected-(MAIN-MASTER-PadAGND)") (class "Default")
      (node (ref "MAIN-MASTER") (pin "AGND") (pinfunction "AGND_AGND") (pintype "bidirectional+no_connect"))
    )
    (net (code "211") (name "unconnected-(MAIN-MASTER-PadAREF)") (class "Default")
      (node (ref "MAIN-MASTER") (pin "AREF") (pinfunction "AREF_AREF") (pintype "bidirectional+no_connect"))
    )
    (net (code "212") (name "unconnected-(MAIN-MASTER-PadDC)") (class "Default")
      (node (ref "MAIN-MASTER") (pin "DC") (pinfunction "DC_DC") (pintype "bidirectional+no_connect"))
    )
    (net (code "213") (name "unconnected-(MAIN-MASTER-PadDE)") (class "Default")
      (node (ref "MAIN-MASTER") (pin "DE") (pinfunction "DE_DE") (pintype "bidirectional+no_connect"))
    )
    (net (code "214") (name "unconnected-(MAIN-MASTER-PadDO)") (class "Default")
      (node (ref "MAIN-MASTER") (pin "DO") (pinfunction "DO_DO") (pintype "bidirectional+no_connect"))
    )
    (net (code "215") (name "unconnected-(MAIN-MASTER-PadPGM)") (class "Default")
      (node (ref "MAIN-MASTER") (pin "PGM") (pinfunction "PGM_PGM") (pintype "bidirectional+no_connect"))
    )
    (net (code "216") (name "unconnected-(MAIN-MASTER-PadRESET)") (class "Default")
      (node (ref "MAIN-MASTER") (pin "RESET") (pinfunction "RESET_RESET") (pintype "bidirectional+no_connect"))
    )
    (net (code "217") (name "unconnected-(MAIN-MASTER-PadVBAT)") (class "Default")
      (node (ref "MAIN-MASTER") (pin "VBAT") (pinfunction "VBAT_VBAT") (pintype "bidirectional+no_connect"))
    )
    (net (code "218") (name "unconnected-(MAIN-MASTER-PadVUSB)") (class "Default")
      (node (ref "MAIN-MASTER") (pin "VUSB") (pinfunction "VUSB_VUSB") (pintype "bidirectional+no_connect"))
    )
    (net (code "219") (name "unconnected-(MULTI17-1-I6-Pad3)") (class "Default")
      (node (ref "MULTI17-1") (pin "3") (pinfunction "I6_3") (pintype "unspecified+no_connect"))
    )
    (net (code "220") (name "unconnected-(MULTI17-1-I7-Pad2)") (class "Default")
      (node (ref "MULTI17-1") (pin "2") (pinfunction "I7_2") (pintype "unspecified+no_connect"))
    )
    (net (code "221") (name "unconnected-(MULTI17-1-I14-Pad17)") (class "Default")
      (node (ref "MULTI17-1") (pin "17") (pinfunction "I14_17") (pintype "unspecified+no_connect"))
    )
    (net (code "222") (name "unconnected-(MULTI17-1-I15-Pad16)") (class "Default")
      (node (ref "MULTI17-1") (pin "16") (pinfunction "I15_16") (pintype "unspecified+no_connect"))
    )
    (net (code "223") (name "unconnected-(P10-Pad2)") (class "Default")
      (node (ref "P10") (pin "2") (pinfunction "2_2") (pintype "input+no_connect"))
    )
    (net (code "224") (name "unconnected-(P11-Pad2)") (class "Default")
      (node (ref "P11") (pin "2") (pinfunction "2_2") (pintype "input+no_connect"))
    )
  )
)
